# utilidong-lipo-charger-mk-2_0.net
KiCad netlist of a schematic drawn in EAGLE
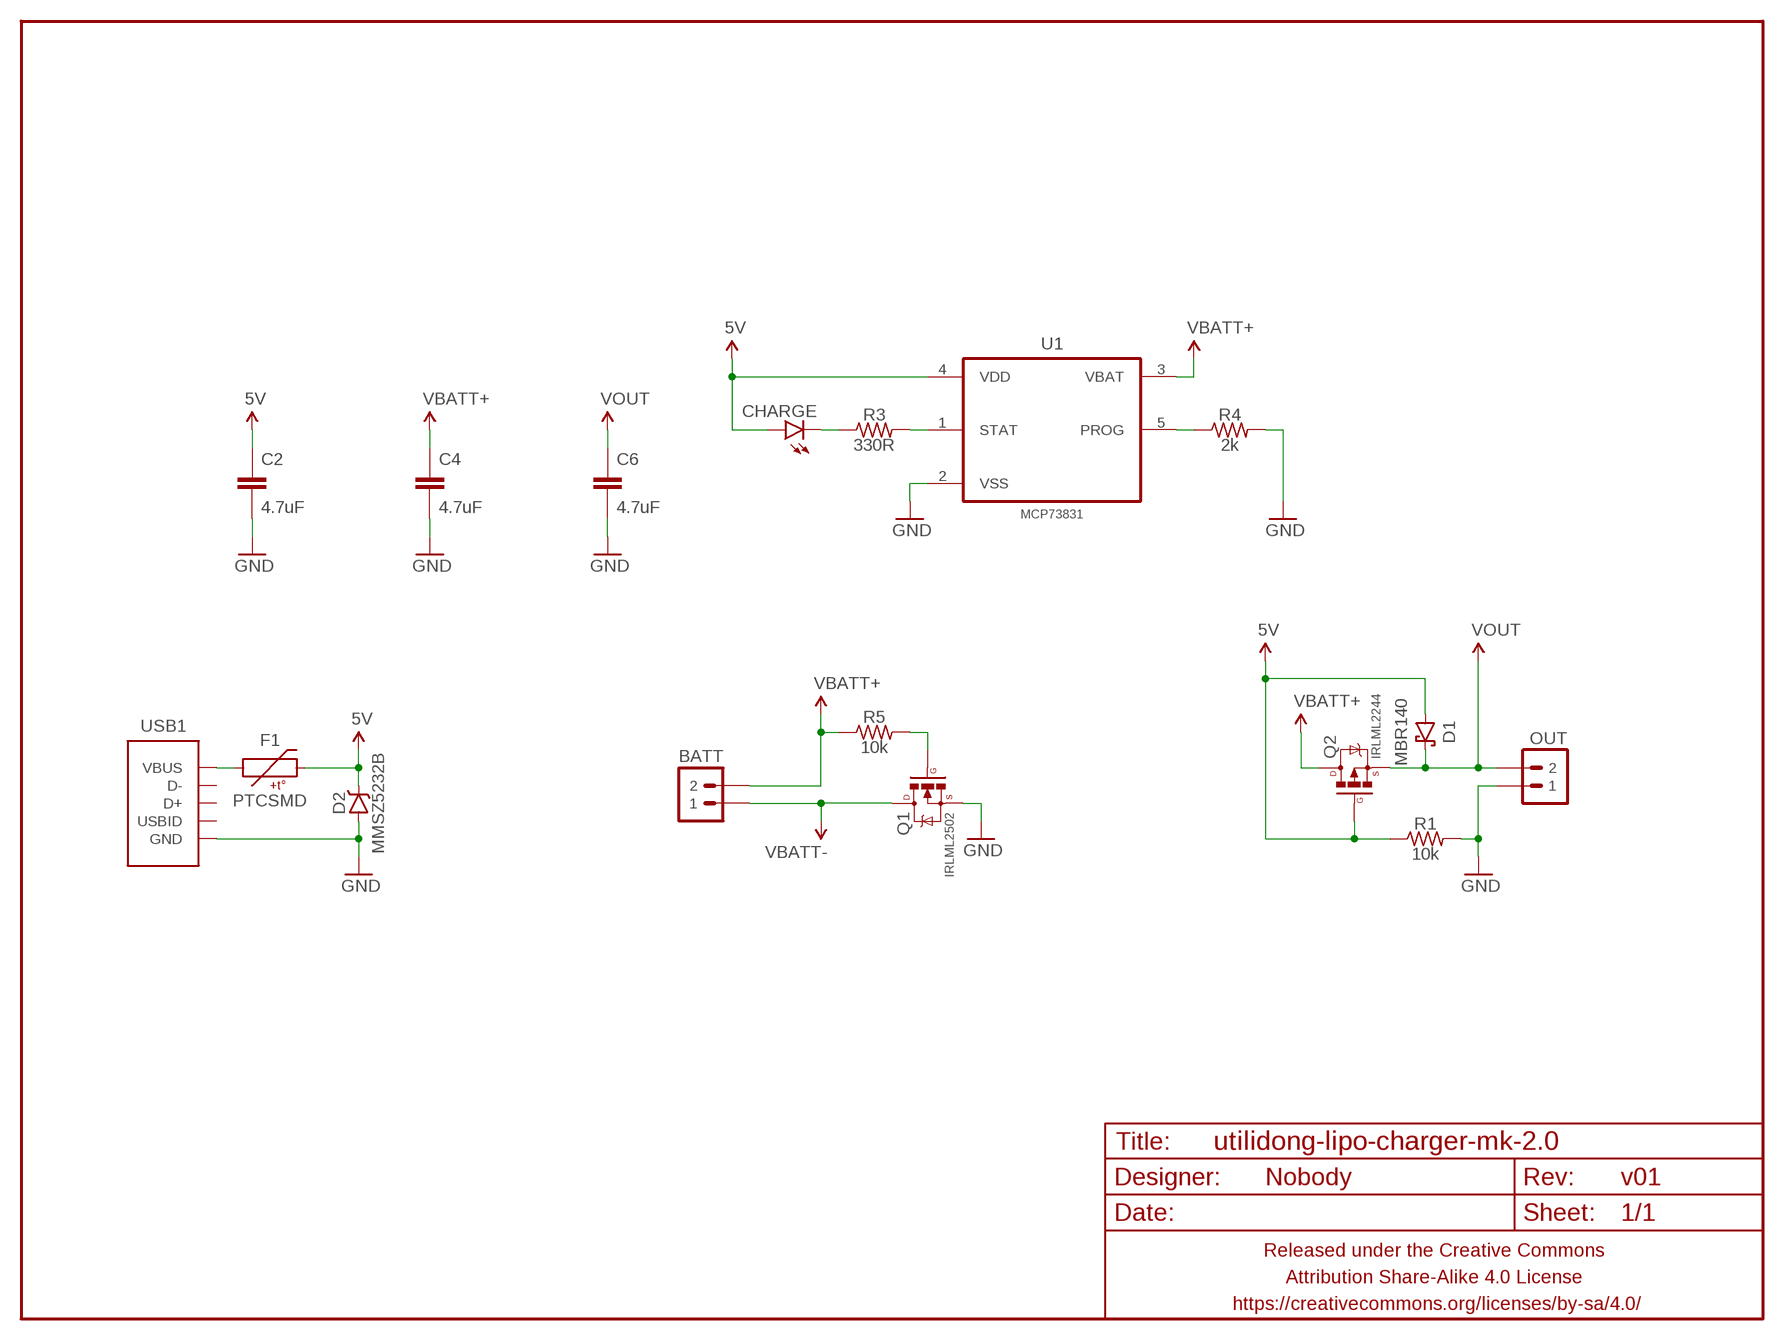
[diagram p0: schematic, sheet 1]

(export (version "E")
  (design (tool "Eeschema 10.0.6"))
  (components
    (comp (ref "BATT")
      (value "M02PTH-CENTERED-R+")
      (footprint "eagle-import:1X02-CENTER-R+")
      (libsource (lib "eagle-import") (part "M02PTH-CENTERED-R+"))
    )
    (comp (ref "C2")
      (value "4.7uF")
      (footprint "eagle-import:C1206")
      (libsource (lib "eagle-import") (part "CAPACITOR-CERAMICC1206"))
    )
    (comp (ref "C4")
      (value "4.7uF")
      (footprint "eagle-import:C1206")
      (libsource (lib "eagle-import") (part "CAPACITOR-CERAMICC1206"))
    )
    (comp (ref "C6")
      (value "4.7uF")
      (footprint "eagle-import:C1206")
      (libsource (lib "eagle-import") (part "CAPACITOR-CERAMICC1206"))
    )
    (comp (ref "CHARGE")
      (value "LED1206")
      (footprint "eagle-import:LED-1206")
      (libsource (lib "eagle-import") (part "LED1206"))
    )
    (comp (ref "D1")
      (value "MBR140")
      (footprint "eagle-import:SMA-DIODE-SCHOTTKY")
      (libsource (lib "eagle-import") (part "DIODE-SCHOTTKYSMA"))
    )
    (comp (ref "D2")
      (value "MMSZ5232B")
      (footprint "eagle-import:SOD123-ZENER")
      (libsource (lib "eagle-import") (part "DIODE-ZENERSOD123"))
    )
    (comp (ref "F1")
      (value "PTCSMD")
      (footprint "eagle-import:PTC-1206")
      (libsource (lib "eagle-import") (part "PTCSMD"))
    )
    (comp (ref "FRAME1")
      (value "FRAME-LETTERNO_PACKAGE")
      (footprint "eagle-import:DUMMY")
      (fields (field (name "DESIGNER") "Nobody"))
      (libsource (lib "eagle-import") (part "FRAME-LETTERNO_PACKAGE"))
    )
    (comp (ref "OUT")
      (value "M02PTH-CENTERED-R+")
      (footprint "eagle-import:1X02-CENTER-R+")
      (libsource (lib "eagle-import") (part "M02PTH-CENTERED-R+"))
    )
    (comp (ref "Q1")
      (value "IRLML2502")
      (footprint "eagle-import:SOT23")
      (libsource (lib "eagle-import") (part "MOSFET-NCHANNELBSS138"))
    )
    (comp (ref "Q2")
      (value "IRLML2244")
      (footprint "eagle-import:SOT23-3")
      (libsource (lib "eagle-import") (part "MOSFET-PCHANNELIRLML2244"))
    )
    (comp (ref "R1")
      (value "10k")
      (footprint "eagle-import:R0805")
      (libsource (lib "eagle-import") (part "RESISTORR0805"))
    )
    (comp (ref "R3")
      (value "330R")
      (footprint "eagle-import:R0805")
      (libsource (lib "eagle-import") (part "RESISTORR0805"))
    )
    (comp (ref "R4")
      (value "2k")
      (footprint "eagle-import:R0805")
      (libsource (lib "eagle-import") (part "RESISTORR0805"))
    )
    (comp (ref "R5")
      (value "10k")
      (footprint "eagle-import:R0805")
      (libsource (lib "eagle-import") (part "RESISTORR0805"))
    )
    (comp (ref "U1")
      (value "MCP73831")
      (footprint "eagle-import:SOT95P280X145-5N")
      (fields (field (name "MPN") "MCP73831T-2ACI/OT"))
      (libsource (lib "eagle-import") (part "MCP73831T-2ACI/OT"))
    )
    (comp (ref "USB1")
      (value "USB-ABCOMBO")
      (footprint "eagle-import:USB-MICRO-B-FCI-CUTOUT")
      (libsource (lib "eagle-import") (part "USB-ABCOMBO"))
    )
  )
  (nets
    (net (code "1") (name "5V") (class "Default")
      (node (ref "C2") (pin "1") (pinfunction "1_1") (pintype "passive"))
      (node (ref "CHARGE") (pin "A") (pinfunction "A_A") (pintype "passive"))
      (node (ref "D1") (pin "A") (pinfunction "A_A") (pintype "passive"))
      (node (ref "D2") (pin "C") (pinfunction "C_C") (pintype "passive"))
      (node (ref "F1") (pin "2") (pinfunction "2_2") (pintype "passive"))
      (node (ref "Q2") (pin "1") (pinfunction "G_1") (pintype "passive"))
      (node (ref "R1") (pin "1") (pinfunction "1_1") (pintype "passive"))
      (node (ref "U1") (pin "4") (pinfunction "VDD_4") (pintype "power_in"))
    )
    (net (code "2") (name "GND") (class "Default")
      (node (ref "C2") (pin "2") (pinfunction "2_2") (pintype "passive"))
      (node (ref "C4") (pin "2") (pinfunction "2_2") (pintype "passive"))
      (node (ref "C6") (pin "2") (pinfunction "2_2") (pintype "passive"))
      (node (ref "D2") (pin "A") (pinfunction "A_A") (pintype "passive"))
      (node (ref "OUT") (pin "1") (pinfunction "1_1") (pintype "passive"))
      (node (ref "Q1") (pin "2") (pinfunction "S_2") (pintype "passive"))
      (node (ref "R1") (pin "2") (pinfunction "2_2") (pintype "passive"))
      (node (ref "R4") (pin "2") (pinfunction "2_2") (pintype "passive"))
      (node (ref "U1") (pin "2") (pinfunction "VSS_2") (pintype "power_in"))
      (node (ref "USB1") (pin "5") (pinfunction "GND_5") (pintype "bidirectional"))
      (node (ref "USB1") (pin "P$1") (pinfunction "GND_P$1") (pintype "bidirectional"))
      (node (ref "USB1") (pin "P$2") (pinfunction "GND_P$2") (pintype "bidirectional"))
    )
    (net (code "3") (name "Net-(CHARGE-PadC)") (class "Default")
      (node (ref "CHARGE") (pin "C") (pinfunction "C_C") (pintype "passive"))
      (node (ref "R3") (pin "1") (pinfunction "1_1") (pintype "passive"))
    )
    (net (code "4") (name "Net-(Q1-G)") (class "Default")
      (node (ref "Q1") (pin "1") (pinfunction "G_1") (pintype "passive"))
      (node (ref "R5") (pin "2") (pinfunction "2_2") (pintype "passive"))
    )
    (net (code "5") (name "Net-(U1-PROG)") (class "Default")
      (node (ref "R4") (pin "1") (pinfunction "1_1") (pintype "passive"))
      (node (ref "U1") (pin "5") (pinfunction "PROG_5") (pintype "input"))
    )
    (net (code "6") (name "Net-(U1-STAT)") (class "Default")
      (node (ref "R3") (pin "2") (pinfunction "2_2") (pintype "passive"))
      (node (ref "U1") (pin "1") (pinfunction "STAT_1") (pintype "output"))
    )
    (net (code "7") (name "Net-(USB1-VBUS)") (class "Default")
      (node (ref "F1") (pin "1") (pinfunction "1_1") (pintype "passive"))
      (node (ref "USB1") (pin "1") (pinfunction "VBUS_1") (pintype "bidirectional"))
    )
    (net (code "8") (name "VBATT+") (class "Default")
      (node (ref "BATT") (pin "2") (pinfunction "2_2") (pintype "passive"))
      (node (ref "C4") (pin "1") (pinfunction "1_1") (pintype "passive"))
      (node (ref "Q2") (pin "3") (pinfunction "D_3") (pintype "passive"))
      (node (ref "R5") (pin "1") (pinfunction "1_1") (pintype "passive"))
      (node (ref "U1") (pin "3") (pinfunction "VBAT_3") (pintype "output"))
    )
    (net (code "9") (name "VBATT-") (class "Default")
      (node (ref "BATT") (pin "1") (pinfunction "1_1") (pintype "passive"))
      (node (ref "Q1") (pin "3") (pinfunction "D_3") (pintype "passive"))
    )
    (net (code "10") (name "VOUT") (class "Default")
      (node (ref "C6") (pin "1") (pinfunction "1_1") (pintype "passive"))
      (node (ref "D1") (pin "C") (pinfunction "C_C") (pintype "passive"))
      (node (ref "OUT") (pin "2") (pinfunction "2_2") (pintype "passive"))
      (node (ref "Q2") (pin "2") (pinfunction "S_2") (pintype "passive"))
    )
    (net (code "11") (name "unconnected-(USB1-D+-Pad3)") (class "Default")
      (node (ref "USB1") (pin "3") (pinfunction "D+_3") (pintype "bidirectional"))
    )
    (net (code "12") (name "unconnected-(USB1-D--Pad2)") (class "Default")
      (node (ref "USB1") (pin "2") (pinfunction "D-_2") (pintype "bidirectional"))
    )
    (net (code "13") (name "unconnected-(USB1-USBID-Pad4)") (class "Default")
      (node (ref "USB1") (pin "4") (pinfunction "USBID_4") (pintype "bidirectional"))
    )
  )
)
